# PWM_Soldeerbout.net
KiCad netlist of a schematic drawn in Altium Designer
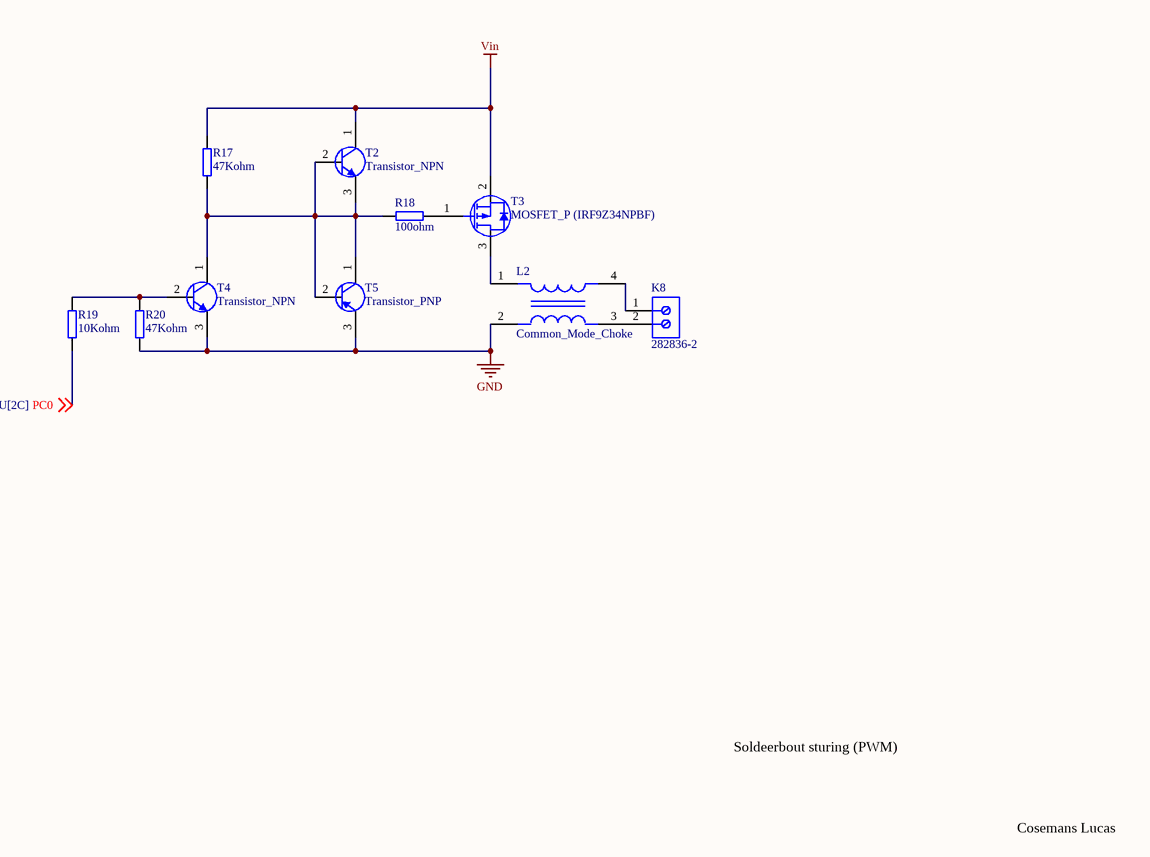
[diagram p0: PWM_Soldeerbout.SchDoc]

(export (version "E")
  (design (tool "Eeschema 10.0.6"))
  (components
    (comp (ref "K8")
      (value "282836-2")
      (footprint "2x1 Schroef pin TECO-282836-2_V")
      (description "Female Header, Pitch 5 mm, 1 x 2 Position, Height 10 mm, Tail Length 3.5 mm, Rohs, Bulk")
      (fields (field (name "VOLTAGE") "300V") (field (name "MANUFACTURER") "TE Connectivity"))
      (libsource (lib "Schematic_soldeerstation") (part "2x1 schroef pin"))
    )
    (comp (ref "L2")
      (value "Common_Mode_Choke")
      (footprint "2545")
      (libsource (lib "Schematic_soldeerstation") (part "Common_Mode_Choke"))
    )
    (comp (ref "R17")
      (value "47Kohm")
      (footprint "R_0805_M")
      (fields (field (name "MANUFACTURER") "Vishay Dale") (field (name "PART NUMBER") "CRCW08050000Z0EA"))
      (libsource (lib "Schematic_soldeerstation") (part "Resistor"))
    )
    (comp (ref "R18")
      (value "100ohm")
      (footprint "R_0805_M")
      (fields (field (name "MANUFACTURER") "Vishay Dale") (field (name "PART NUMBER") "CRCW08050000Z0EA"))
      (libsource (lib "Schematic_soldeerstation") (part "Resistor"))
    )
    (comp (ref "R19")
      (value "10Kohm")
      (footprint "R_0805_M")
      (fields (field (name "MANUFACTURER") "Vishay Dale") (field (name "PART NUMBER") "CRCW08050000Z0EA"))
      (libsource (lib "Schematic_soldeerstation") (part "Resistor"))
    )
    (comp (ref "R20")
      (value "47Kohm")
      (footprint "R_0805_M")
      (fields (field (name "MANUFACTURER") "Vishay Dale") (field (name "PART NUMBER") "CRCW08050000Z0EA"))
      (libsource (lib "Schematic_soldeerstation") (part "Resistor"))
    )
    (comp (ref "T2")
      (value "Transistor_NPN")
      (footprint "SOT_23")
      (fields (field (name "MANUFACTURER") "On Semiconductor") (field (name "PARTNUMBER") "BC547C"))
      (libsource (lib "Schematic_soldeerstation") (part "Transistor_NPN"))
    )
    (comp (ref "T3")
      (value "MOSFET_P (IRF9Z34NPBF)")
      (footprint "TO_252")
      (fields (field (name "MANUFACTURER") "Fairchild Semiconductor"))
      (libsource (lib "Schematic_soldeerstation") (part "MOSFET_P (IRF9Z34NPBF)"))
    )
    (comp (ref "T4")
      (value "Transistor_NPN")
      (footprint "SOT_23")
      (fields (field (name "MANUFACTURER") "On Semiconductor") (field (name "PARTNUMBER") "BC547C"))
      (libsource (lib "Schematic_soldeerstation") (part "Transistor_NPN"))
    )
    (comp (ref "T5")
      (value "Transistor_PNP")
      (footprint "SOT_23")
      (fields (field (name "MANUFACTURER") "On Semiconductor") (field (name "PARTNUMBER") "BC557C"))
      (libsource (lib "Schematic_soldeerstation") (part "Transistor_PNP"))
    )
  )
  (nets
    (net (code "1") (name "GND") (class "Default")
      (node (ref "L2") (pin "2") (pinfunction "2_2") (pintype "passive"))
      (node (ref "R20") (pin "1") (pinfunction "1_1") (pintype "passive"))
      (node (ref "T4") (pin "3") (pinfunction "E_3") (pintype "passive"))
      (node (ref "T5") (pin "3") (pinfunction "E_3") (pintype "passive"))
    )
    (net (code "2") (name "Net-(K8-Pad1)") (class "Default")
      (node (ref "K8") (pin "1") (pinfunction "1_1") (pintype "passive"))
      (node (ref "L2") (pin "4") (pinfunction "4_4") (pintype "passive"))
    )
    (net (code "3") (name "Net-(K8-Pad2)") (class "Default")
      (node (ref "K8") (pin "2") (pinfunction "2_2") (pintype "passive"))
      (node (ref "L2") (pin "3") (pinfunction "3_3") (pintype "passive"))
    )
    (net (code "4") (name "Net-(T2-B)") (class "Default")
      (node (ref "R17") (pin "1") (pinfunction "1_1") (pintype "passive"))
      (node (ref "R18") (pin "1") (pinfunction "1_1") (pintype "passive"))
      (node (ref "T2") (pin "2") (pinfunction "B_2") (pintype "passive"))
      (node (ref "T2") (pin "3") (pinfunction "E_3") (pintype "passive"))
      (node (ref "T4") (pin "1") (pinfunction "C_1") (pintype "passive"))
      (node (ref "T5") (pin "1") (pinfunction "C_1") (pintype "passive"))
      (node (ref "T5") (pin "2") (pinfunction "B_2") (pintype "passive"))
    )
    (net (code "5") (name "Net-(T3-DRAIN)") (class "Default")
      (node (ref "L2") (pin "1") (pinfunction "1_1") (pintype "passive"))
      (node (ref "T3") (pin "3") (pinfunction "DRAIN_3") (pintype "passive"))
    )
    (net (code "6") (name "Net-(T3-GATE)") (class "Default")
      (node (ref "R18") (pin "2") (pinfunction "2_2") (pintype "passive"))
      (node (ref "T3") (pin "1") (pinfunction "GATE_1") (pintype "passive"))
    )
    (net (code "7") (name "Net-(T4-B)") (class "Default")
      (node (ref "R19") (pin "2") (pinfunction "2_2") (pintype "passive"))
      (node (ref "R20") (pin "2") (pinfunction "2_2") (pintype "passive"))
      (node (ref "T4") (pin "2") (pinfunction "B_2") (pintype "passive"))
    )
    (net (code "8") (name "PC0") (class "Default")
      (node (ref "R19") (pin "1") (pinfunction "1_1") (pintype "passive"))
    )
    (net (code "9") (name "Vin") (class "Default")
      (node (ref "R17") (pin "2") (pinfunction "2_2") (pintype "passive"))
      (node (ref "T2") (pin "1") (pinfunction "C_1") (pintype "passive"))
      (node (ref "T3") (pin "2") (pinfunction "SOURCE_2") (pintype "passive"))
    )
  )
)
